# MSP432.net
KiCad netlist of a schematic drawn in Altium Designer
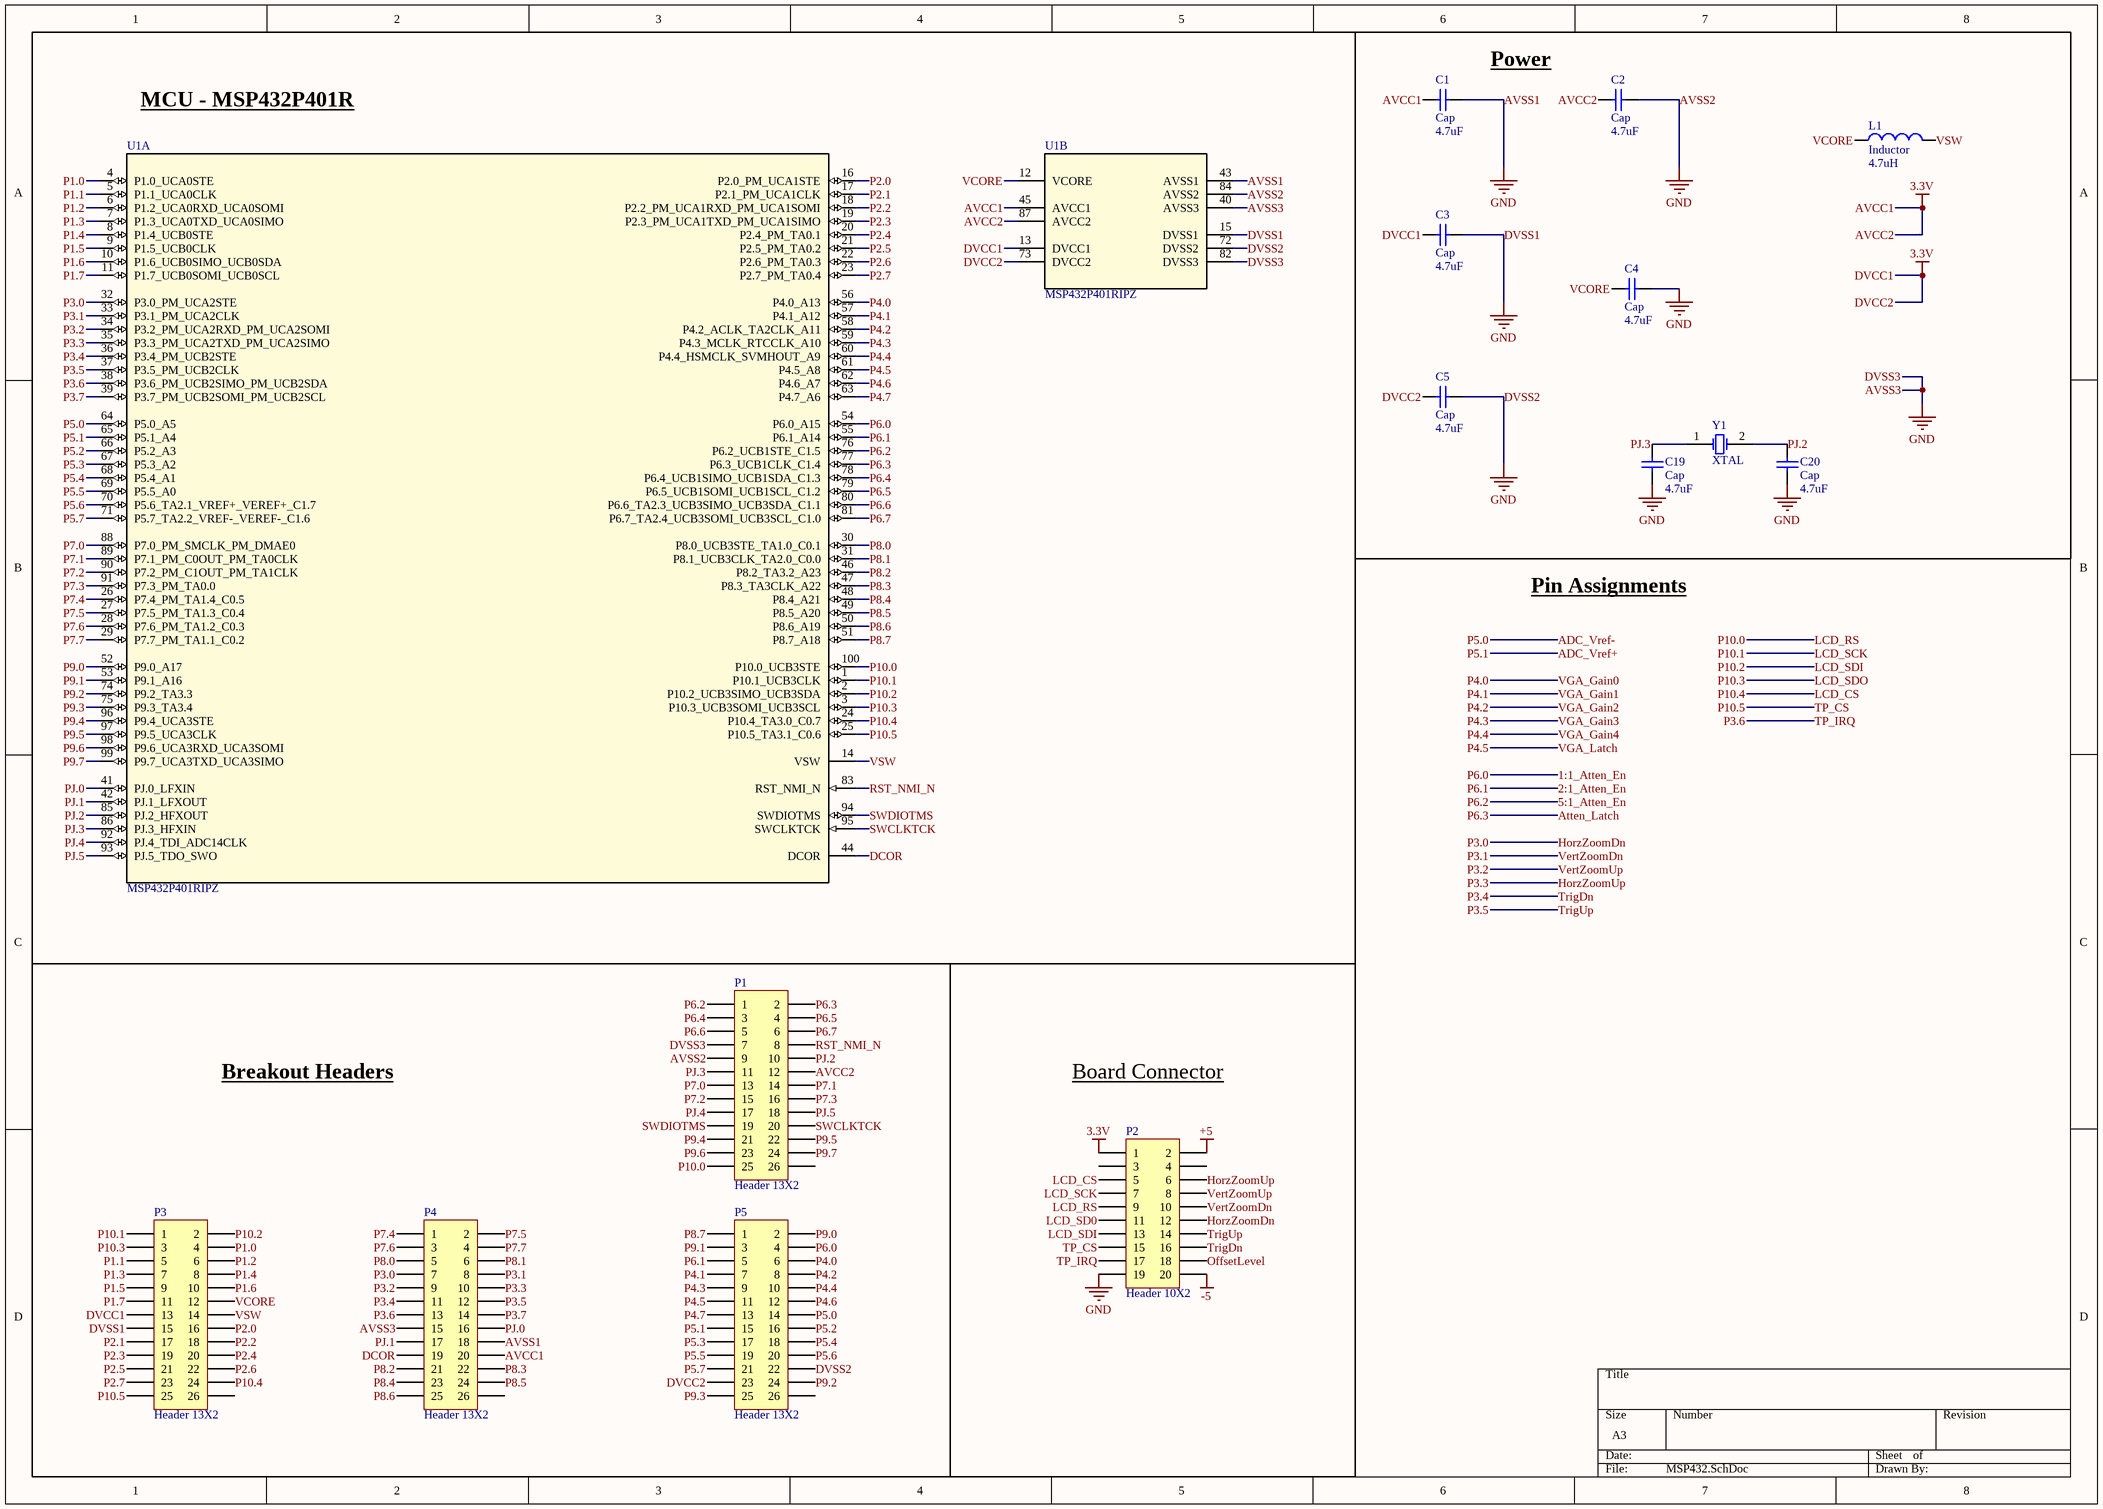
[diagram p0: MSP432.SchDoc]

(export (version "E")
  (design (tool "Eeschema 10.0.6"))
  (components
    (comp (ref "C1")
      (value "Cap")
      (footprint "6-0805_N")
      (description "Capacitor")
      (fields (field (name "ALTIUM_VALUE") "4.7uF") (field (name "PUBLISHER") "Altium Limited"))
      (libsource (lib "Miscellaneous Devices") (part "Cap"))
    )
    (comp (ref "C2")
      (value "Cap")
      (footprint "6-0805_N")
      (description "Capacitor")
      (fields (field (name "ALTIUM_VALUE") "4.7uF") (field (name "PUBLISHER") "Altium Limited"))
      (libsource (lib "Miscellaneous Devices") (part "Cap"))
    )
    (comp (ref "C3")
      (value "Cap")
      (footprint "6-0805_N")
      (description "Capacitor")
      (fields (field (name "ALTIUM_VALUE") "4.7uF") (field (name "PUBLISHER") "Altium Limited"))
      (libsource (lib "Miscellaneous Devices") (part "Cap"))
    )
    (comp (ref "C4")
      (value "Cap")
      (footprint "6-0805_N")
      (description "Capacitor")
      (fields (field (name "ALTIUM_VALUE") "4.7uF") (field (name "PUBLISHER") "Altium Limited"))
      (libsource (lib "Miscellaneous Devices") (part "Cap"))
    )
    (comp (ref "C5")
      (value "Cap")
      (footprint "6-0805_N")
      (description "Capacitor")
      (fields (field (name "ALTIUM_VALUE") "4.7uF") (field (name "PUBLISHER") "Altium Limited"))
      (libsource (lib "Miscellaneous Devices") (part "Cap"))
    )
    (comp (ref "C19")
      (value "Cap")
      (footprint "6-0805_N")
      (description "Capacitor")
      (fields (field (name "ALTIUM_VALUE") "4.7uF") (field (name "PUBLISHER") "Altium Limited"))
      (libsource (lib "Miscellaneous Devices") (part "Cap"))
    )
    (comp (ref "C20")
      (value "Cap")
      (footprint "6-0805_N")
      (description "Capacitor")
      (fields (field (name "ALTIUM_VALUE") "4.7uF") (field (name "PUBLISHER") "Altium Limited"))
      (libsource (lib "Miscellaneous Devices") (part "Cap"))
    )
    (comp (ref "L1")
      (value "Inductor")
      (footprint "6-0805_N")
      (fields (field (name "ALTIUM_VALUE") "4.7uH") (field (name "PUBLISHER") "Altium Limited"))
      (libsource (lib "Miscellaneous Devices") (part "Inductor"))
    )
    (comp (ref "P1")
      (value "Header 13X2")
      (footprint "HDR2X13")
      (description "Header, 13-Pin, Dual row")
      (fields (field (name "PUBLISHER") "Altium Limited"))
      (libsource (lib "Miscellaneous Connectors") (part "Header 13X2"))
    )
    (comp (ref "P2")
      (value "Header 10X2")
      (footprint "HDR2X10")
      (description "Header, 10-Pin, Dual row")
      (fields (field (name "PUBLISHER") "Altium Limited"))
      (libsource (lib "Miscellaneous Connectors") (part "Header 10X2"))
    )
    (comp (ref "P3")
      (value "Header 13X2")
      (footprint "HDR2X13")
      (description "Header, 13-Pin, Dual row")
      (fields (field (name "PUBLISHER") "Altium Limited"))
      (libsource (lib "Miscellaneous Connectors") (part "Header 13X2"))
    )
    (comp (ref "P4")
      (value "Header 13X2")
      (footprint "HDR2X13")
      (description "Header, 13-Pin, Dual row")
      (fields (field (name "PUBLISHER") "Altium Limited"))
      (libsource (lib "Miscellaneous Connectors") (part "Header 13X2"))
    )
    (comp (ref "P5")
      (value "Header 13X2")
      (footprint "HDR2X13")
      (description "Header, 13-Pin, Dual row")
      (fields (field (name "PUBLISHER") "Altium Limited"))
      (libsource (lib "Miscellaneous Connectors") (part "Header 13X2"))
    )
    (comp (ref "U1")
      (value "MSP432P401RIPZ")
      (footprint "PZ0100A_N")
      (description "No Description Available")
      (fields
        (field (name "PARTNUMBER") "XMS432P401RIPZR")
        (field (name "MANUFACTURER") "Texas Instruments")
        (field (name "COPYRIGHT") "Copyright (C) 2018 Accelerated Designs. All rights reserved")
      )
      (libsource (lib "MSP432") (part "MSP432P401RIPZ"))
    )
    (comp (ref "Y1")
      (value "XTAL")
      (footprint "HC-49U")
      (description "Crystal Oscillator")
      (fields (field (name "PUBLISHER") "Altium Limited"))
      (libsource (lib "ECE LIB new") (part "XTAL"))
    )
  )
  (nets
    (net (code "1") (name "+5") (class "Default")
      (node (ref "P2") (pin "2") (pinfunction "2_2") (pintype "passive"))
    )
    (net (code "2") (name "-5") (class "Default")
      (node (ref "P2") (pin "20") (pinfunction "20_20") (pintype "passive"))
    )
    (net (code "3") (name "/1:1_Atten_En") (class "Default")
      (node (ref "P5") (pin "4") (pinfunction "4_4") (pintype "passive"))
      (node (ref "U1") (pin "54") (pinfunction "P6.0_A15_54") (pintype "bidirectional"))
    )
    (net (code "4") (name "/2:1_Atten_En") (class "Default")
      (node (ref "P5") (pin "5") (pinfunction "5_5") (pintype "passive"))
      (node (ref "U1") (pin "55") (pinfunction "P6.1_A14_55") (pintype "bidirectional"))
    )
    (net (code "5") (name "/5:1_Atten_En") (class "Default")
      (node (ref "P1") (pin "1") (pinfunction "1_1") (pintype "passive"))
      (node (ref "U1") (pin "76") (pinfunction "P6.2_UCB1STE_C1.5_76") (pintype "bidirectional"))
    )
    (net (code "6") (name "/ADC_Vref+") (class "Default")
      (node (ref "P5") (pin "15") (pinfunction "15_15") (pintype "passive"))
      (node (ref "U1") (pin "65") (pinfunction "P5.1_A4_65") (pintype "bidirectional"))
    )
    (net (code "7") (name "/ADC_Vref-") (class "Default")
      (node (ref "P5") (pin "14") (pinfunction "14_14") (pintype "passive"))
      (node (ref "U1") (pin "64") (pinfunction "P5.0_A5_64") (pintype "bidirectional"))
    )
    (net (code "8") (name "/Atten_Latch") (class "Default")
      (node (ref "P1") (pin "2") (pinfunction "2_2") (pintype "passive"))
      (node (ref "U1") (pin "77") (pinfunction "P6.3_UCB1CLK_C1.4_77") (pintype "bidirectional"))
    )
    (net (code "9") (name "/DCOR") (class "Default")
      (node (ref "P4") (pin "19") (pinfunction "19_19") (pintype "passive"))
      (node (ref "U1") (pin "44") (pinfunction "DCOR_44") (pintype "passive"))
    )
    (net (code "10") (name "/HorzZoomDn") (class "Default")
      (node (ref "P2") (pin "12") (pinfunction "12_12") (pintype "passive"))
      (node (ref "P4") (pin "7") (pinfunction "7_7") (pintype "passive"))
      (node (ref "U1") (pin "32") (pinfunction "P3.0_PM_UCA2STE_32") (pintype "bidirectional"))
    )
    (net (code "11") (name "/HorzZoomUp") (class "Default")
      (node (ref "P2") (pin "6") (pinfunction "6_6") (pintype "passive"))
      (node (ref "P4") (pin "10") (pinfunction "10_10") (pintype "passive"))
      (node (ref "U1") (pin "35") (pinfunction "P3.3_PM_UCA2TXD_PM_UCA2SIMO_35") (pintype "bidirectional"))
    )
    (net (code "12") (name "/LCD_CS") (class "Default")
      (node (ref "P2") (pin "5") (pinfunction "5_5") (pintype "passive"))
      (node (ref "P3") (pin "24") (pinfunction "24_24") (pintype "passive"))
      (node (ref "U1") (pin "24") (pinfunction "P10.4_TA3.0_C0.7_24") (pintype "bidirectional"))
    )
    (net (code "13") (name "/LCD_RS") (class "Default")
      (node (ref "P1") (pin "25") (pinfunction "25_25") (pintype "passive"))
      (node (ref "P2") (pin "9") (pinfunction "9_9") (pintype "passive"))
      (node (ref "U1") (pin "100") (pinfunction "P10.0_UCB3STE_100") (pintype "bidirectional"))
    )
    (net (code "14") (name "/LCD_SCK") (class "Default")
      (node (ref "P2") (pin "7") (pinfunction "7_7") (pintype "passive"))
      (node (ref "P3") (pin "1") (pinfunction "1_1") (pintype "passive"))
      (node (ref "U1") (pin "1") (pinfunction "P10.1_UCB3CLK_1") (pintype "bidirectional"))
    )
    (net (code "15") (name "/LCD_SD0") (class "Default")
      (node (ref "P2") (pin "11") (pinfunction "11_11") (pintype "passive"))
    )
    (net (code "16") (name "/LCD_SDI") (class "Default")
      (node (ref "P2") (pin "13") (pinfunction "13_13") (pintype "passive"))
      (node (ref "P3") (pin "2") (pinfunction "2_2") (pintype "passive"))
      (node (ref "U1") (pin "2") (pinfunction "P10.2_UCB3SIMO_UCB3SDA_2") (pintype "bidirectional"))
    )
    (net (code "17") (name "/LCD_SDO") (class "Default")
      (node (ref "P3") (pin "3") (pinfunction "3_3") (pintype "passive"))
      (node (ref "U1") (pin "3") (pinfunction "P10.3_UCB3SOMI_UCB3SCL_3") (pintype "bidirectional"))
    )
    (net (code "18") (name "/OffsetLevel") (class "Default")
      (node (ref "P2") (pin "18") (pinfunction "18_18") (pintype "passive"))
    )
    (net (code "19") (name "/P1.0") (class "Default")
      (node (ref "P3") (pin "4") (pinfunction "4_4") (pintype "passive"))
      (node (ref "U1") (pin "4") (pinfunction "P1.0_UCA0STE_4") (pintype "bidirectional"))
    )
    (net (code "20") (name "/P1.1") (class "Default")
      (node (ref "P3") (pin "5") (pinfunction "5_5") (pintype "passive"))
      (node (ref "U1") (pin "5") (pinfunction "P1.1_UCA0CLK_5") (pintype "bidirectional"))
    )
    (net (code "21") (name "/P1.2") (class "Default")
      (node (ref "P3") (pin "6") (pinfunction "6_6") (pintype "passive"))
      (node (ref "U1") (pin "6") (pinfunction "P1.2_UCA0RXD_UCA0SOMI_6") (pintype "bidirectional"))
    )
    (net (code "22") (name "/P1.3") (class "Default")
      (node (ref "P3") (pin "7") (pinfunction "7_7") (pintype "passive"))
      (node (ref "U1") (pin "7") (pinfunction "P1.3_UCA0TXD_UCA0SIMO_7") (pintype "bidirectional"))
    )
    (net (code "23") (name "/P1.4") (class "Default")
      (node (ref "P3") (pin "8") (pinfunction "8_8") (pintype "passive"))
      (node (ref "U1") (pin "8") (pinfunction "P1.4_UCB0STE_8") (pintype "bidirectional"))
    )
    (net (code "24") (name "/P1.5") (class "Default")
      (node (ref "P3") (pin "9") (pinfunction "9_9") (pintype "passive"))
      (node (ref "U1") (pin "9") (pinfunction "P1.5_UCB0CLK_9") (pintype "bidirectional"))
    )
    (net (code "25") (name "/P1.6") (class "Default")
      (node (ref "P3") (pin "10") (pinfunction "10_10") (pintype "passive"))
      (node (ref "U1") (pin "10") (pinfunction "P1.6_UCB0SIMO_UCB0SDA_10") (pintype "bidirectional"))
    )
    (net (code "26") (name "/P1.7") (class "Default")
      (node (ref "P3") (pin "11") (pinfunction "11_11") (pintype "passive"))
      (node (ref "U1") (pin "11") (pinfunction "P1.7_UCB0SOMI_UCB0SCL_11") (pintype "bidirectional"))
    )
    (net (code "27") (name "/P2.0") (class "Default")
      (node (ref "P3") (pin "16") (pinfunction "16_16") (pintype "passive"))
      (node (ref "U1") (pin "16") (pinfunction "P2.0_PM_UCA1STE_16") (pintype "bidirectional"))
    )
    (net (code "28") (name "/P2.1") (class "Default")
      (node (ref "P3") (pin "17") (pinfunction "17_17") (pintype "passive"))
      (node (ref "U1") (pin "17") (pinfunction "P2.1_PM_UCA1CLK_17") (pintype "bidirectional"))
    )
    (net (code "29") (name "/P2.2") (class "Default")
      (node (ref "P3") (pin "18") (pinfunction "18_18") (pintype "passive"))
      (node (ref "U1") (pin "18") (pinfunction "P2.2_PM_UCA1RXD_PM_UCA1SOMI_18") (pintype "bidirectional"))
    )
    (net (code "30") (name "/P2.3") (class "Default")
      (node (ref "P3") (pin "19") (pinfunction "19_19") (pintype "passive"))
      (node (ref "U1") (pin "19") (pinfunction "P2.3_PM_UCA1TXD_PM_UCA1SIMO_19") (pintype "bidirectional"))
    )
    (net (code "31") (name "/P2.4") (class "Default")
      (node (ref "P3") (pin "20") (pinfunction "20_20") (pintype "passive"))
      (node (ref "U1") (pin "20") (pinfunction "P2.4_PM_TA0.1_20") (pintype "bidirectional"))
    )
    (net (code "32") (name "/P2.5") (class "Default")
      (node (ref "P3") (pin "21") (pinfunction "21_21") (pintype "passive"))
      (node (ref "U1") (pin "21") (pinfunction "P2.5_PM_TA0.2_21") (pintype "bidirectional"))
    )
    (net (code "33") (name "/P2.6") (class "Default")
      (node (ref "P3") (pin "22") (pinfunction "22_22") (pintype "passive"))
      (node (ref "U1") (pin "22") (pinfunction "P2.6_PM_TA0.3_22") (pintype "bidirectional"))
    )
    (net (code "34") (name "/P2.7") (class "Default")
      (node (ref "P3") (pin "23") (pinfunction "23_23") (pintype "passive"))
      (node (ref "U1") (pin "23") (pinfunction "P2.7_PM_TA0.4_23") (pintype "bidirectional"))
    )
    (net (code "35") (name "/P3.1") (class "Default")
      (node (ref "P2") (pin "10") (pinfunction "10_10") (pintype "passive"))
      (node (ref "P4") (pin "8") (pinfunction "8_8") (pintype "passive"))
      (node (ref "U1") (pin "33") (pinfunction "P3.1_PM_UCA2CLK_33") (pintype "bidirectional"))
    )
    (net (code "36") (name "/P3.2") (class "Default")
      (node (ref "P2") (pin "8") (pinfunction "8_8") (pintype "passive"))
      (node (ref "P4") (pin "9") (pinfunction "9_9") (pintype "passive"))
      (node (ref "U1") (pin "34") (pinfunction "P3.2_PM_UCA2RXD_PM_UCA2SOMI_34") (pintype "bidirectional"))
    )
    (net (code "37") (name "/P3.4") (class "Default")
      (node (ref "P2") (pin "16") (pinfunction "16_16") (pintype "passive"))
      (node (ref "P4") (pin "11") (pinfunction "11_11") (pintype "passive"))
      (node (ref "U1") (pin "36") (pinfunction "P3.4_PM_UCB2STE_36") (pintype "bidirectional"))
    )
    (net (code "38") (name "/P3.5") (class "Default")
      (node (ref "P2") (pin "14") (pinfunction "14_14") (pintype "passive"))
      (node (ref "P4") (pin "12") (pinfunction "12_12") (pintype "passive"))
      (node (ref "U1") (pin "37") (pinfunction "P3.5_PM_UCB2CLK_37") (pintype "bidirectional"))
    )
    (net (code "39") (name "/P3.6") (class "Default")
      (node (ref "P2") (pin "17") (pinfunction "17_17") (pintype "passive"))
      (node (ref "P4") (pin "13") (pinfunction "13_13") (pintype "passive"))
      (node (ref "U1") (pin "38") (pinfunction "P3.6_PM_UCB2SIMO_PM_UCB2SDA_38") (pintype "bidirectional"))
    )
    (net (code "40") (name "/P3.7") (class "Default")
      (node (ref "P4") (pin "14") (pinfunction "14_14") (pintype "passive"))
      (node (ref "U1") (pin "39") (pinfunction "P3.7_PM_UCB2SOMI_PM_UCB2SCL_39") (pintype "bidirectional"))
    )
    (net (code "41") (name "/P4.0") (class "Default")
      (node (ref "P5") (pin "6") (pinfunction "6_6") (pintype "passive"))
      (node (ref "U1") (pin "56") (pinfunction "P4.0_A13_56") (pintype "bidirectional"))
    )
    (net (code "42") (name "/P4.1") (class "Default")
      (node (ref "P5") (pin "7") (pinfunction "7_7") (pintype "passive"))
      (node (ref "U1") (pin "57") (pinfunction "P4.1_A12_57") (pintype "bidirectional"))
    )
    (net (code "43") (name "/P4.2") (class "Default")
      (node (ref "P5") (pin "8") (pinfunction "8_8") (pintype "passive"))
      (node (ref "U1") (pin "58") (pinfunction "P4.2_ACLK_TA2CLK_A11_58") (pintype "bidirectional"))
    )
    (net (code "44") (name "/P4.3") (class "Default")
      (node (ref "P5") (pin "9") (pinfunction "9_9") (pintype "passive"))
      (node (ref "U1") (pin "59") (pinfunction "P4.3_MCLK_RTCCLK_A10_59") (pintype "bidirectional"))
    )
    (net (code "45") (name "/P4.4") (class "Default")
      (node (ref "P5") (pin "10") (pinfunction "10_10") (pintype "passive"))
      (node (ref "U1") (pin "60") (pinfunction "P4.4_HSMCLK_SVMHOUT_A9_60") (pintype "bidirectional"))
    )
    (net (code "46") (name "/P4.5") (class "Default")
      (node (ref "P5") (pin "11") (pinfunction "11_11") (pintype "passive"))
      (node (ref "U1") (pin "61") (pinfunction "P4.5_A8_61") (pintype "bidirectional"))
    )
    (net (code "47") (name "/P4.6") (class "Default")
      (node (ref "P5") (pin "12") (pinfunction "12_12") (pintype "passive"))
      (node (ref "U1") (pin "62") (pinfunction "P4.6_A7_62") (pintype "bidirectional"))
    )
    (net (code "48") (name "/P4.7") (class "Default")
      (node (ref "P5") (pin "13") (pinfunction "13_13") (pintype "passive"))
      (node (ref "U1") (pin "63") (pinfunction "P4.7_A6_63") (pintype "bidirectional"))
    )
    (net (code "49") (name "/P5.2") (class "Default")
      (node (ref "P5") (pin "16") (pinfunction "16_16") (pintype "passive"))
      (node (ref "U1") (pin "66") (pinfunction "P5.2_A3_66") (pintype "bidirectional"))
    )
    (net (code "50") (name "/P5.3") (class "Default")
      (node (ref "P5") (pin "17") (pinfunction "17_17") (pintype "passive"))
      (node (ref "U1") (pin "67") (pinfunction "P5.3_A2_67") (pintype "bidirectional"))
    )
    (net (code "51") (name "/P5.4") (class "Default")
      (node (ref "P5") (pin "18") (pinfunction "18_18") (pintype "passive"))
      (node (ref "U1") (pin "68") (pinfunction "P5.4_A1_68") (pintype "bidirectional"))
    )
    (net (code "52") (name "/P5.5") (class "Default")
      (node (ref "P5") (pin "19") (pinfunction "19_19") (pintype "passive"))
      (node (ref "U1") (pin "69") (pinfunction "P5.5_A0_69") (pintype "bidirectional"))
    )
    (net (code "53") (name "/P5.6") (class "Default")
      (node (ref "P5") (pin "20") (pinfunction "20_20") (pintype "passive"))
      (node (ref "U1") (pin "70") (pinfunction "P5.6_TA2.1_VREF+_VEREF+_C1.7_70") (pintype "bidirectional"))
    )
    (net (code "54") (name "/P5.7") (class "Default")
      (node (ref "P5") (pin "21") (pinfunction "21_21") (pintype "passive"))
      (node (ref "U1") (pin "71") (pinfunction "P5.7_TA2.2_VREF-_VEREF-_C1.6_71") (pintype "bidirectional"))
    )
    (net (code "55") (name "/P6.4") (class "Default")
      (node (ref "P1") (pin "3") (pinfunction "3_3") (pintype "passive"))
      (node (ref "U1") (pin "78") (pinfunction "P6.4_UCB1SIMO_UCB1SDA_C1.3_78") (pintype "bidirectional"))
    )
    (net (code "56") (name "/P6.5") (class "Default")
      (node (ref "P1") (pin "4") (pinfunction "4_4") (pintype "passive"))
      (node (ref "U1") (pin "79") (pinfunction "P6.5_UCB1SOMI_UCB1SCL_C1.2_79") (pintype "bidirectional"))
    )
    (net (code "57") (name "/P6.6") (class "Default")
      (node (ref "P1") (pin "5") (pinfunction "5_5") (pintype "passive"))
      (node (ref "U1") (pin "80") (pinfunction "P6.6_TA2.3_UCB3SIMO_UCB3SDA_C1.1_80") (pintype "bidirectional"))
    )
    (net (code "58") (name "/P6.7") (class "Default")
      (node (ref "P1") (pin "6") (pinfunction "6_6") (pintype "passive"))
      (node (ref "U1") (pin "81") (pinfunction "P6.7_TA2.4_UCB3SOMI_UCB3SCL_C1.0_81") (pintype "bidirectional"))
    )
    (net (code "59") (name "/P7.0") (class "Default")
      (node (ref "P1") (pin "13") (pinfunction "13_13") (pintype "passive"))
      (node (ref "U1") (pin "88") (pinfunction "P7.0_PM_SMCLK_PM_DMAE0_88") (pintype "bidirectional"))
    )
    (net (code "60") (name "/P7.1") (class "Default")
      (node (ref "P1") (pin "14") (pinfunction "14_14") (pintype "passive"))
      (node (ref "U1") (pin "89") (pinfunction "P7.1_PM_C0OUT_PM_TA0CLK_89") (pintype "bidirectional"))
    )
    (net (code "61") (name "/P7.2") (class "Default")
      (node (ref "P1") (pin "15") (pinfunction "15_15") (pintype "passive"))
      (node (ref "U1") (pin "90") (pinfunction "P7.2_PM_C1OUT_PM_TA1CLK_90") (pintype "bidirectional"))
    )
    (net (code "62") (name "/P7.3") (class "Default")
      (node (ref "P1") (pin "16") (pinfunction "16_16") (pintype "passive"))
      (node (ref "U1") (pin "91") (pinfunction "P7.3_PM_TA0.0_91") (pintype "bidirectional"))
    )
    (net (code "63") (name "/P7.4") (class "Default")
      (node (ref "P4") (pin "1") (pinfunction "1_1") (pintype "passive"))
      (node (ref "U1") (pin "26") (pinfunction "P7.4_PM_TA1.4_C0.5_26") (pintype "bidirectional"))
    )
    (net (code "64") (name "/P7.5") (class "Default")
      (node (ref "P4") (pin "2") (pinfunction "2_2") (pintype "passive"))
      (node (ref "U1") (pin "27") (pinfunction "P7.5_PM_TA1.3_C0.4_27") (pintype "bidirectional"))
    )
    (net (code "65") (name "/P7.6") (class "Default")
      (node (ref "P4") (pin "3") (pinfunction "3_3") (pintype "passive"))
      (node (ref "U1") (pin "28") (pinfunction "P7.6_PM_TA1.2_C0.3_28") (pintype "bidirectional"))
    )
    (net (code "66") (name "/P7.7") (class "Default")
      (node (ref "P4") (pin "4") (pinfunction "4_4") (pintype "passive"))
      (node (ref "U1") (pin "29") (pinfunction "P7.7_PM_TA1.1_C0.2_29") (pintype "bidirectional"))
    )
    (net (code "67") (name "/P8.0") (class "Default")
      (node (ref "P4") (pin "5") (pinfunction "5_5") (pintype "passive"))
      (node (ref "U1") (pin "30") (pinfunction "P8.0_UCB3STE_TA1.0_C0.1_30") (pintype "bidirectional"))
    )
    (net (code "68") (name "/P8.1") (class "Default")
      (node (ref "P4") (pin "6") (pinfunction "6_6") (pintype "passive"))
      (node (ref "U1") (pin "31") (pinfunction "P8.1_UCB3CLK_TA2.0_C0.0_31") (pintype "bidirectional"))
    )
    (net (code "69") (name "/P8.2") (class "Default")
      (node (ref "P4") (pin "21") (pinfunction "21_21") (pintype "passive"))
      (node (ref "U1") (pin "46") (pinfunction "P8.2_TA3.2_A23_46") (pintype "bidirectional"))
    )
    (net (code "70") (name "/P8.3") (class "Default")
      (node (ref "P4") (pin "22") (pinfunction "22_22") (pintype "passive"))
      (node (ref "U1") (pin "47") (pinfunction "P8.3_TA3CLK_A22_47") (pintype "bidirectional"))
    )
    (net (code "71") (name "/P8.4") (class "Default")
      (node (ref "P4") (pin "23") (pinfunction "23_23") (pintype "passive"))
      (node (ref "U1") (pin "48") (pinfunction "P8.4_A21_48") (pintype "bidirectional"))
    )
    (net (code "72") (name "/P8.5") (class "Default")
      (node (ref "P4") (pin "24") (pinfunction "24_24") (pintype "passive"))
      (node (ref "U1") (pin "49") (pinfunction "P8.5_A20_49") (pintype "bidirectional"))
    )
    (net (code "73") (name "/P8.6") (class "Default")
      (node (ref "P4") (pin "25") (pinfunction "25_25") (pintype "passive"))
      (node (ref "U1") (pin "50") (pinfunction "P8.6_A19_50") (pintype "bidirectional"))
    )
    (net (code "74") (name "/P8.7") (class "Default")
      (node (ref "P5") (pin "1") (pinfunction "1_1") (pintype "passive"))
      (node (ref "U1") (pin "51") (pinfunction "P8.7_A18_51") (pintype "bidirectional"))
    )
    (net (code "75") (name "/P9.0") (class "Default")
      (node (ref "P5") (pin "2") (pinfunction "2_2") (pintype "passive"))
      (node (ref "U1") (pin "52") (pinfunction "P9.0_A17_52") (pintype "bidirectional"))
    )
    (net (code "76") (name "/P9.1") (class "Default")
      (node (ref "P5") (pin "3") (pinfunction "3_3") (pintype "passive"))
      (node (ref "U1") (pin "53") (pinfunction "P9.1_A16_53") (pintype "bidirectional"))
    )
    (net (code "77") (name "/P9.2") (class "Default")
      (node (ref "P5") (pin "24") (pinfunction "24_24") (pintype "passive"))
      (node (ref "U1") (pin "74") (pinfunction "P9.2_TA3.3_74") (pintype "bidirectional"))
    )
    (net (code "78") (name "/P9.3") (class "Default")
      (node (ref "P5") (pin "25") (pinfunction "25_25") (pintype "passive"))
      (node (ref "U1") (pin "75") (pinfunction "P9.3_TA3.4_75") (pintype "bidirectional"))
    )
    (net (code "79") (name "/P9.4") (class "Default")
      (node (ref "P1") (pin "21") (pinfunction "21_21") (pintype "passive"))
      (node (ref "U1") (pin "96") (pinfunction "P9.4_UCA3STE_96") (pintype "bidirectional"))
    )
    (net (code "80") (name "/P9.5") (class "Default")
      (node (ref "P1") (pin "22") (pinfunction "22_22") (pintype "passive"))
      (node (ref "U1") (pin "97") (pinfunction "P9.5_UCA3CLK_97") (pintype "bidirectional"))
    )
    (net (code "81") (name "/P9.6") (class "Default")
      (node (ref "P1") (pin "23") (pinfunction "23_23") (pintype "passive"))
      (node (ref "U1") (pin "98") (pinfunction "P9.6_UCA3RXD_UCA3SOMI_98") (pintype "bidirectional"))
    )
    (net (code "82") (name "/P9.7") (class "Default")
      (node (ref "P1") (pin "24") (pinfunction "24_24") (pintype "passive"))
      (node (ref "U1") (pin "99") (pinfunction "P9.7_UCA3TXD_UCA3SIMO_99") (pintype "bidirectional"))
    )
    (net (code "83") (name "/P10.5") (class "Default")
      (node (ref "P2") (pin "15") (pinfunction "15_15") (pintype "passive"))
      (node (ref "P3") (pin "25") (pinfunction "25_25") (pintype "passive"))
      (node (ref "U1") (pin "25") (pinfunction "P10.5_TA3.1_C0.6_25") (pintype "bidirectional"))
    )
    (net (code "84") (name "/PJ.0") (class "Default")
      (node (ref "P4") (pin "16") (pinfunction "16_16") (pintype "passive"))
      (node (ref "U1") (pin "41") (pinfunction "PJ.0_LFXIN_41") (pintype "bidirectional"))
    )
    (net (code "85") (name "/PJ.1") (class "Default")
      (node (ref "P4") (pin "17") (pinfunction "17_17") (pintype "passive"))
      (node (ref "U1") (pin "42") (pinfunction "PJ.1_LFXOUT_42") (pintype "bidirectional"))
    )
    (net (code "86") (name "/PJ.2") (class "Default")
      (node (ref "C20") (pin "1") (pinfunction "1_1") (pintype "passive"))
      (node (ref "P1") (pin "10") (pinfunction "10_10") (pintype "passive"))
      (node (ref "U1") (pin "85") (pinfunction "PJ.2_HFXOUT_85") (pintype "bidirectional"))
      (node (ref "Y1") (pin "2") (pinfunction "OSC2_2") (pintype "passive"))
    )
    (net (code "87") (name "/PJ.3") (class "Default")
      (node (ref "C19") (pin "2") (pinfunction "2_2") (pintype "passive"))
      (node (ref "P1") (pin "11") (pinfunction "11_11") (pintype "passive"))
      (node (ref "U1") (pin "86") (pinfunction "PJ.3_HFXIN_86") (pintype "bidirectional"))
      (node (ref "Y1") (pin "1") (pinfunction "OSC1_1") (pintype "passive"))
    )
    (net (code "88") (name "/PJ.4") (class "Default")
      (node (ref "P1") (pin "17") (pinfunction "17_17") (pintype "passive"))
      (node (ref "U1") (pin "92") (pinfunction "PJ.4_TDI_ADC14CLK_92") (pintype "bidirectional"))
    )
    (net (code "89") (name "/PJ.5") (class "Default")
      (node (ref "P1") (pin "18") (pinfunction "18_18") (pintype "passive"))
      (node (ref "U1") (pin "93") (pinfunction "PJ.5_TDO_SWO_93") (pintype "bidirectional"))
    )
    (net (code "90") (name "/RST_NMI_N") (class "Default")
      (node (ref "P1") (pin "8") (pinfunction "8_8") (pintype "passive"))
      (node (ref "U1") (pin "83") (pinfunction "RST_NMI_N_83") (pintype "input"))
    )
    (net (code "91") (name "/SWCLKTCK") (class "Default")
      (node (ref "P1") (pin "20") (pinfunction "20_20") (pintype "passive"))
      (node (ref "U1") (pin "95") (pinfunction "SWCLKTCK_95") (pintype "input"))
    )
    (net (code "92") (name "/SWDIOTMS") (class "Default")
      (node (ref "P1") (pin "19") (pinfunction "19_19") (pintype "passive"))
      (node (ref "U1") (pin "94") (pinfunction "SWDIOTMS_94") (pintype "bidirectional"))
    )
    (net (code "93") (name "/VCORE") (class "Default")
      (node (ref "C4") (pin "1") (pinfunction "1_1") (pintype "passive"))
      (node (ref "L1") (pin "1") (pinfunction "1_1") (pintype "passive"))
      (node (ref "P3") (pin "12") (pinfunction "12_12") (pintype "passive"))
      (node (ref "U1") (pin "12") (pinfunction "VCORE_12") (pintype "power_in"))
    )
    (net (code "94") (name "/VSW") (class "Default")
      (node (ref "L1") (pin "2") (pinfunction "2_2") (pintype "passive"))
      (node (ref "P3") (pin "14") (pinfunction "14_14") (pintype "passive"))
      (node (ref "U1") (pin "14") (pinfunction "VSW_14") (pintype "passive"))
    )
    (net (code "95") (name "3.3V") (class "Default")
      (node (ref "C1") (pin "1") (pinfunction "1_1") (pintype "passive"))
      (node (ref "C2") (pin "1") (pinfunction "1_1") (pintype "passive"))
      (node (ref "C3") (pin "1") (pinfunction "1_1") (pintype "passive"))
      (node (ref "C5") (pin "1") (pinfunction "1_1") (pintype "passive"))
      (node (ref "P1") (pin "12") (pinfunction "12_12") (pintype "passive"))
      (node (ref "P2") (pin "1") (pinfunction "1_1") (pintype "passive"))
      (node (ref "P3") (pin "13") (pinfunction "13_13") (pintype "passive"))
      (node (ref "P4") (pin "20") (pinfunction "20_20") (pintype "passive"))
      (node (ref "P5") (pin "23") (pinfunction "23_23") (pintype "passive"))
      (node (ref "U1") (pin "13") (pinfunction "DVCC1_13") (pintype "power_in"))
      (node (ref "U1") (pin "45") (pinfunction "AVCC1_45") (pintype "power_in"))
      (node (ref "U1") (pin "73") (pinfunction "DVCC2_73") (pintype "power_in"))
      (node (ref "U1") (pin "87") (pinfunction "AVCC2_87") (pintype "power_in"))
    )
    (net (code "96") (name "GND") (class "Default")
      (node (ref "C1") (pin "2") (pinfunction "2_2") (pintype "passive"))
      (node (ref "C19") (pin "1") (pinfunction "1_1") (pintype "passive"))
      (node (ref "C2") (pin "2") (pinfunction "2_2") (pintype "passive"))
      (node (ref "C20") (pin "2") (pinfunction "2_2") (pintype "passive"))
      (node (ref "C3") (pin "2") (pinfunction "2_2") (pintype "passive"))
      (node (ref "C4") (pin "2") (pinfunction "2_2") (pintype "passive"))
      (node (ref "C5") (pin "2") (pinfunction "2_2") (pintype "passive"))
      (node (ref "P1") (pin "7") (pinfunction "7_7") (pintype "passive"))
      (node (ref "P1") (pin "9") (pinfunction "9_9") (pintype "passive"))
      (node (ref "P2") (pin "19") (pinfunction "19_19") (pintype "passive"))
      (node (ref "P3") (pin "15") (pinfunction "15_15") (pintype "passive"))
      (node (ref "P4") (pin "15") (pinfunction "15_15") (pintype "passive"))
      (node (ref "P4") (pin "18") (pinfunction "18_18") (pintype "passive"))
      (node (ref "P5") (pin "22") (pinfunction "22_22") (pintype "passive"))
      (node (ref "U1") (pin "15") (pinfunction "DVSS1_15") (pintype "power_in"))
      (node (ref "U1") (pin "40") (pinfunction "AVSS3_40") (pintype "power_in"))
      (node (ref "U1") (pin "43") (pinfunction "AVSS1_43") (pintype "power_in"))
      (node (ref "U1") (pin "72") (pinfunction "DVSS2_72") (pintype "power_in"))
      (node (ref "U1") (pin "82") (pinfunction "DVSS3_82") (pintype "power_in"))
      (node (ref "U1") (pin "84") (pinfunction "AVSS2_84") (pintype "power_in"))
    )
    (net (code "97") (name "unconnected-(P1-Pad26)") (class "Default")
      (node (ref "P1") (pin "26") (pinfunction "26_26") (pintype "passive"))
    )
    (net (code "98") (name "unconnected-(P2-Pad3)") (class "Default")
      (node (ref "P2") (pin "3") (pinfunction "3_3") (pintype "passive"))
    )
    (net (code "99") (name "unconnected-(P2-Pad4)") (class "Default")
      (node (ref "P2") (pin "4") (pinfunction "4_4") (pintype "passive"))
    )
    (net (code "100") (name "unconnected-(P3-Pad26)") (class "Default")
      (node (ref "P3") (pin "26") (pinfunction "26_26") (pintype "passive"))
    )
    (net (code "101") (name "unconnected-(P4-Pad26)") (class "Default")
      (node (ref "P4") (pin "26") (pinfunction "26_26") (pintype "passive"))
    )
    (net (code "102") (name "unconnected-(P5-Pad26)") (class "Default")
      (node (ref "P5") (pin "26") (pinfunction "26_26") (pintype "passive"))
    )
  )
)
